# Power_Input_FET.net
KiCad netlist of a schematic drawn in Altium Designer
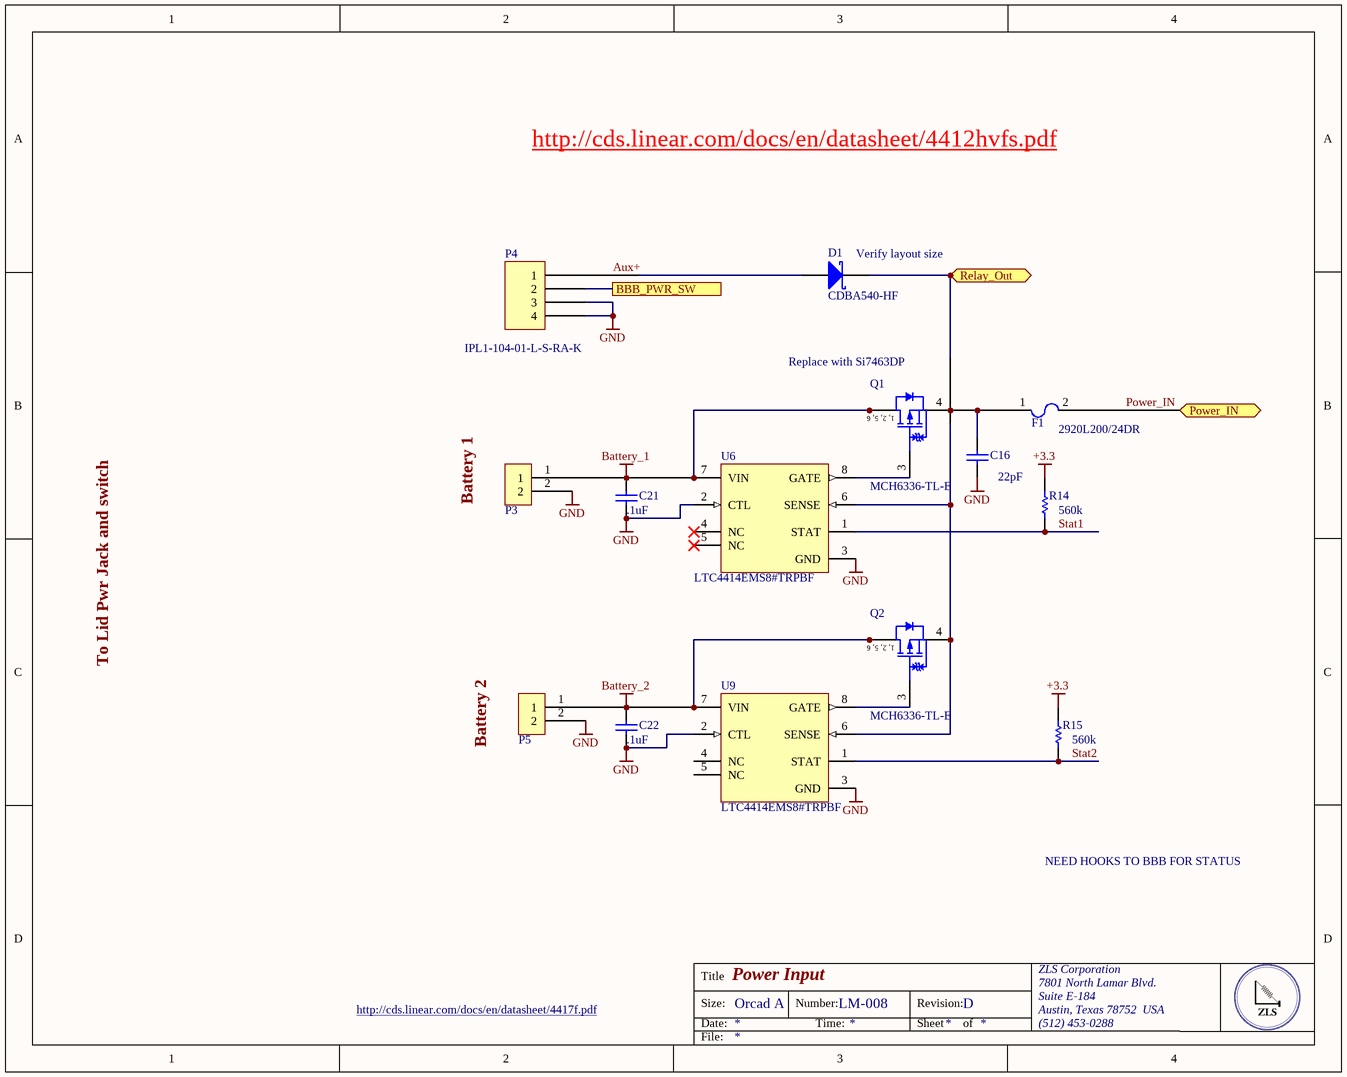
[diagram p0: Power_Input_FET.SchDoc]

(export (version "E")
  (design (tool "Eeschema 10.0.6"))
  (components
    (comp (ref "C16")
      (value "CAP CER 10UF 6.3V X5R 1206")
      (footprint "CAPC1206(3216)130_N")
      (fields
        (field (name "MANUFACTURER") "Taiyo Yuden")
        (field (name "MANUFACTURER PART NUMBER") "JMK316BJ106ML-T")
        (field (name "TOLERANCE") "±20%")
        (field (name "CAPACITANCE") "22pF")
      )
      (libsource (lib "Altium Content Vault") (part "CMP-1037-04913-1"))
    )
    (comp (ref "C21")
      (value "CAP CER 10UF 6.3V X5R 1206")
      (footprint "CAPC1206(3216)130_N")
      (fields
        (field (name "MANUFACTURER") "Taiyo Yuden")
        (field (name "MANUFACTURER PART NUMBER") "JMK316BJ106ML-T")
        (field (name "TOLERANCE") "±20%")
        (field (name "CAPACITANCE") ".1uF")
      )
      (libsource (lib "Altium Content Vault") (part "CMP-1037-04913-1"))
    )
    (comp (ref "C22")
      (value "CAP CER 10UF 6.3V X5R 1206")
      (footprint "CAPC1206(3216)130_N")
      (fields
        (field (name "MANUFACTURER") "Taiyo Yuden")
        (field (name "MANUFACTURER PART NUMBER") "JMK316BJ106ML-T")
        (field (name "TOLERANCE") "±20%")
        (field (name "CAPACITANCE") ".1uF")
      )
      (libsource (lib "Altium Content Vault") (part "CMP-1037-04913-1"))
    )
    (comp (ref "D1")
      (value "CDBA540-HF")
      (footprint "VISH-DO-214AC-2_M")
      (description "DIODE SCHOTTKY 40V 5A DO214AB")
      (fields (field (name "MANUFACTURER") "Comchip Technology"))
      (libsource (lib "Miscellaneous Devices") (part "D Schottky"))
    )
    (comp (ref "F1")
      (value "PCT")
      (footprint "CAPC7451X12N")
      (libsource (lib "ZLS_Schematic_lib") (part "PCT"))
    )
    (comp (ref "P3")
      (value "IPL1-102-01-F-S-RA-K")
      (footprint "IPL1-102-01-F-S-RA-K")
      (libsource (lib "ZLS_Schematic_lib") (part "IPL1-102-01-F-S-RA-K"))
    )
    (comp (ref "P4")
      (value "IPL1-104-01-L-S-RA-K")
      (footprint "IPL1-104-01-L-S-RA-K")
      (fields
        (field (name "MANUFACTURER") "Samtec Inc.")
        (field (name "MANUFACTURER PART NUMBER") "IPL1-104-01-L-S-RA-K")
      )
      (libsource (lib "ZLS_Schematic_lib") (part "IPL1-104-01-L-S-RA-K"))
    )
    (comp (ref "P5")
      (value "IPL1-102-01-F-S-RA-K")
      (footprint "IPL1-102-01-F-S-RA-K")
      (libsource (lib "ZLS_Schematic_lib") (part "IPL1-102-01-F-S-RA-K"))
    )
    (comp (ref "Q1")
      (value "MCH6336-TL-E")
      (footprint "ONSC-MCPH-6_V")
      (description "P-Channel Power MOSFET, -12 V, -5 A, 43 mOhm, Single, 6-Pin MCPH, Pb-Free, Tape and Reel")
      (fields (field (name "MANUFACTURER") "On Semiconductor"))
      (libsource (lib "Altium Content Vault") (part "ONSC-PMOS-6_B"))
    )
    (comp (ref "Q2")
      (value "MCH6336-TL-E")
      (footprint "ONSC-MCPH-6_V")
      (description "P-Channel Power MOSFET, -12 V, -5 A, 43 mOhm, Single, 6-Pin MCPH, Pb-Free, Tape and Reel")
      (fields (field (name "MANUFACTURER") "On Semiconductor"))
      (libsource (lib "Altium Content Vault") (part "ONSC-PMOS-6_B"))
    )
    (comp (ref "R14")
      (value "560k")
      (footprint "RESC0402(1005)_L")
      (fields (field (name "TOLERANCE") "±1%"))
      (libsource (lib "Altium Content Vault") (part "CMP-1011-00927-1"))
    )
    (comp (ref "R15")
      (value "560k")
      (footprint "RESC0402(1005)_L")
      (fields (field (name "TOLERANCE") "±1%"))
      (libsource (lib "Altium Content Vault") (part "CMP-1011-00927-1"))
    )
    (comp (ref "U6")
      (value "LTC4414EMS8#TRPBF")
      (footprint "LT-MS8-8_L")
      (fields (field (name "MANUFACTURER") "Linear Technology"))
      (libsource (lib "Altium Content Vault") (part "CMP-0479-00214-1"))
    )
    (comp (ref "U9")
      (value "LTC4414EMS8#TRPBF")
      (footprint "LT-MS8-8_L")
      (fields (field (name "MANUFACTURER") "Linear Technology"))
      (libsource (lib "Altium Content Vault") (part "CMP-0479-00214-1"))
    )
  )
  (nets
    (net (code "1") (name "+3.3") (class "Default")
      (node (ref "R14") (pin "2") (pinfunction "2_2") (pintype "passive"))
      (node (ref "R15") (pin "2") (pinfunction "2_2") (pintype "passive"))
    )
    (net (code "2") (name "/Aux+") (class "Default")
      (node (ref "D1") (pin "1") (pinfunction "A_1") (pintype "passive"))
      (node (ref "P4") (pin "1") (pinfunction "1_1") (pintype "passive"))
    )
    (net (code "3") (name "/BBB_PWR_SW") (class "Default")
      (node (ref "P4") (pin "2") (pinfunction "2_2") (pintype "passive"))
    )
    (net (code "4") (name "/Power_IN") (class "Default")
      (node (ref "F1") (pin "2") (pinfunction "2_2") (pintype "passive"))
    )
    (net (code "5") (name "/Relay_Out") (class "Default")
      (node (ref "C16") (pin "2") (pinfunction "2_2") (pintype "passive"))
      (node (ref "D1") (pin "2") (pinfunction "K_2") (pintype "passive"))
      (node (ref "F1") (pin "1") (pinfunction "1_1") (pintype "passive"))
      (node (ref "Q1") (pin "4") (pinfunction "S_4") (pintype "passive"))
      (node (ref "Q2") (pin "4") (pinfunction "S_4") (pintype "passive"))
      (node (ref "U6") (pin "6") (pinfunction "SENSE_6") (pintype "input"))
      (node (ref "U9") (pin "6") (pinfunction "SENSE_6") (pintype "input"))
    )
    (net (code "6") (name "/Stat1") (class "Default")
      (node (ref "R14") (pin "1") (pinfunction "1_1") (pintype "passive"))
      (node (ref "U6") (pin "1") (pinfunction "STAT_1") (pintype "open_collector"))
    )
    (net (code "7") (name "/Stat2") (class "Default")
      (node (ref "R15") (pin "1") (pinfunction "1_1") (pintype "passive"))
      (node (ref "U9") (pin "1") (pinfunction "STAT_1") (pintype "open_collector"))
    )
    (net (code "8") (name "Battery_1") (class "Default")
      (node (ref "C21") (pin "2") (pinfunction "2_2") (pintype "passive"))
      (node (ref "P3") (pin "1") (pinfunction "1_1") (pintype "passive"))
      (node (ref "Q1") (pin "1") (pinfunction "D_1") (pintype "passive"))
      (node (ref "Q1") (pin "2") (pinfunction "D_2") (pintype "passive"))
      (node (ref "Q1") (pin "5") (pinfunction "D_5") (pintype "passive"))
      (node (ref "Q1") (pin "6") (pinfunction "D_6") (pintype "passive"))
      (node (ref "U6") (pin "7") (pinfunction "VIN_7") (pintype "power_in"))
    )
    (net (code "9") (name "Battery_2") (class "Default")
      (node (ref "C22") (pin "2") (pinfunction "2_2") (pintype "passive"))
      (node (ref "P5") (pin "1") (pinfunction "1_1") (pintype "passive"))
      (node (ref "Q2") (pin "1") (pinfunction "D_1") (pintype "passive"))
      (node (ref "Q2") (pin "2") (pinfunction "D_2") (pintype "passive"))
      (node (ref "Q2") (pin "5") (pinfunction "D_5") (pintype "passive"))
      (node (ref "Q2") (pin "6") (pinfunction "D_6") (pintype "passive"))
      (node (ref "U9") (pin "7") (pinfunction "VIN_7") (pintype "power_in"))
    )
    (net (code "10") (name "GND") (class "Default")
      (node (ref "C16") (pin "1") (pinfunction "1_1") (pintype "passive"))
      (node (ref "C21") (pin "1") (pinfunction "1_1") (pintype "passive"))
      (node (ref "C22") (pin "1") (pinfunction "1_1") (pintype "passive"))
      (node (ref "P3") (pin "2") (pinfunction "2_2") (pintype "passive"))
      (node (ref "P4") (pin "3") (pinfunction "3_3") (pintype "passive"))
      (node (ref "P4") (pin "4") (pinfunction "4_4") (pintype "passive"))
      (node (ref "P5") (pin "2") (pinfunction "2_2") (pintype "passive"))
      (node (ref "U6") (pin "2") (pinfunction "CTL_2") (pintype "input"))
      (node (ref "U6") (pin "3") (pinfunction "GND_3") (pintype "power_in"))
      (node (ref "U9") (pin "2") (pinfunction "CTL_2") (pintype "input"))
      (node (ref "U9") (pin "3") (pinfunction "GND_3") (pintype "power_in"))
    )
    (net (code "11") (name "Net-(Q1-G)") (class "Default")
      (node (ref "Q1") (pin "3") (pinfunction "G_3") (pintype "passive"))
      (node (ref "U6") (pin "8") (pinfunction "GATE_8") (pintype "output"))
    )
    (net (code "12") (name "Net-(Q2-G)") (class "Default")
      (node (ref "Q2") (pin "3") (pinfunction "G_3") (pintype "passive"))
      (node (ref "U9") (pin "8") (pinfunction "GATE_8") (pintype "output"))
    )
    (net (code "13") (name "unconnected-(U6-NC-Pad4)") (class "Default")
      (node (ref "U6") (pin "4") (pinfunction "NC_4") (pintype "passive+no_connect"))
    )
    (net (code "14") (name "unconnected-(U6-NC-Pad5)") (class "Default")
      (node (ref "U6") (pin "5") (pinfunction "NC_5") (pintype "passive+no_connect"))
    )
    (net (code "15") (name "unconnected-(U9-NC-Pad4)") (class "Default")
      (node (ref "U9") (pin "4") (pinfunction "NC_4") (pintype "passive"))
    )
    (net (code "16") (name "unconnected-(U9-NC-Pad5)") (class "Default")
      (node (ref "U9") (pin "5") (pinfunction "NC_5") (pintype "passive"))
    )
  )
)
